# 008.net
KiCad netlist of a schematic drawn in EAGLE
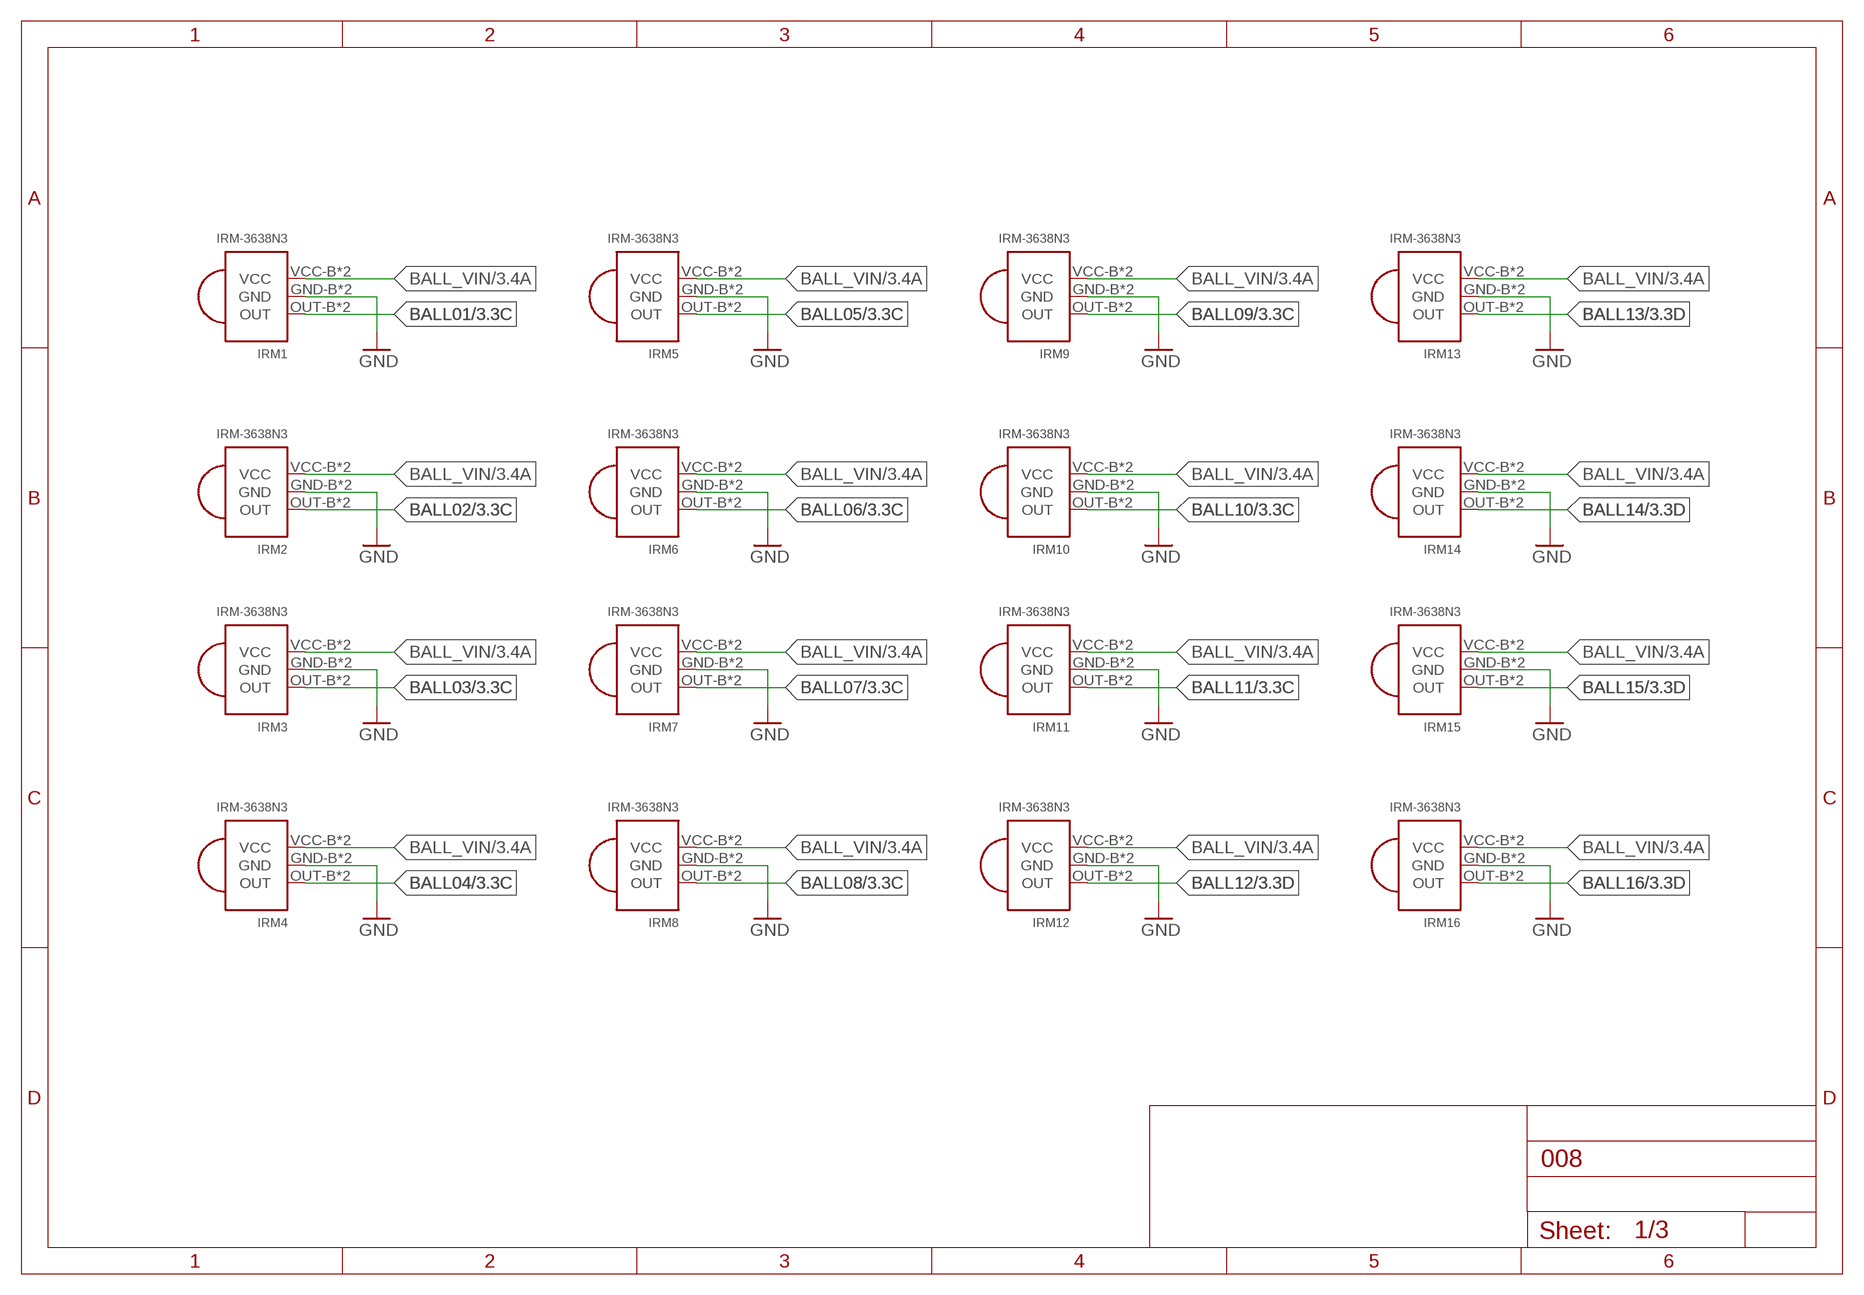
[diagram p0: schematic, sheet 1]
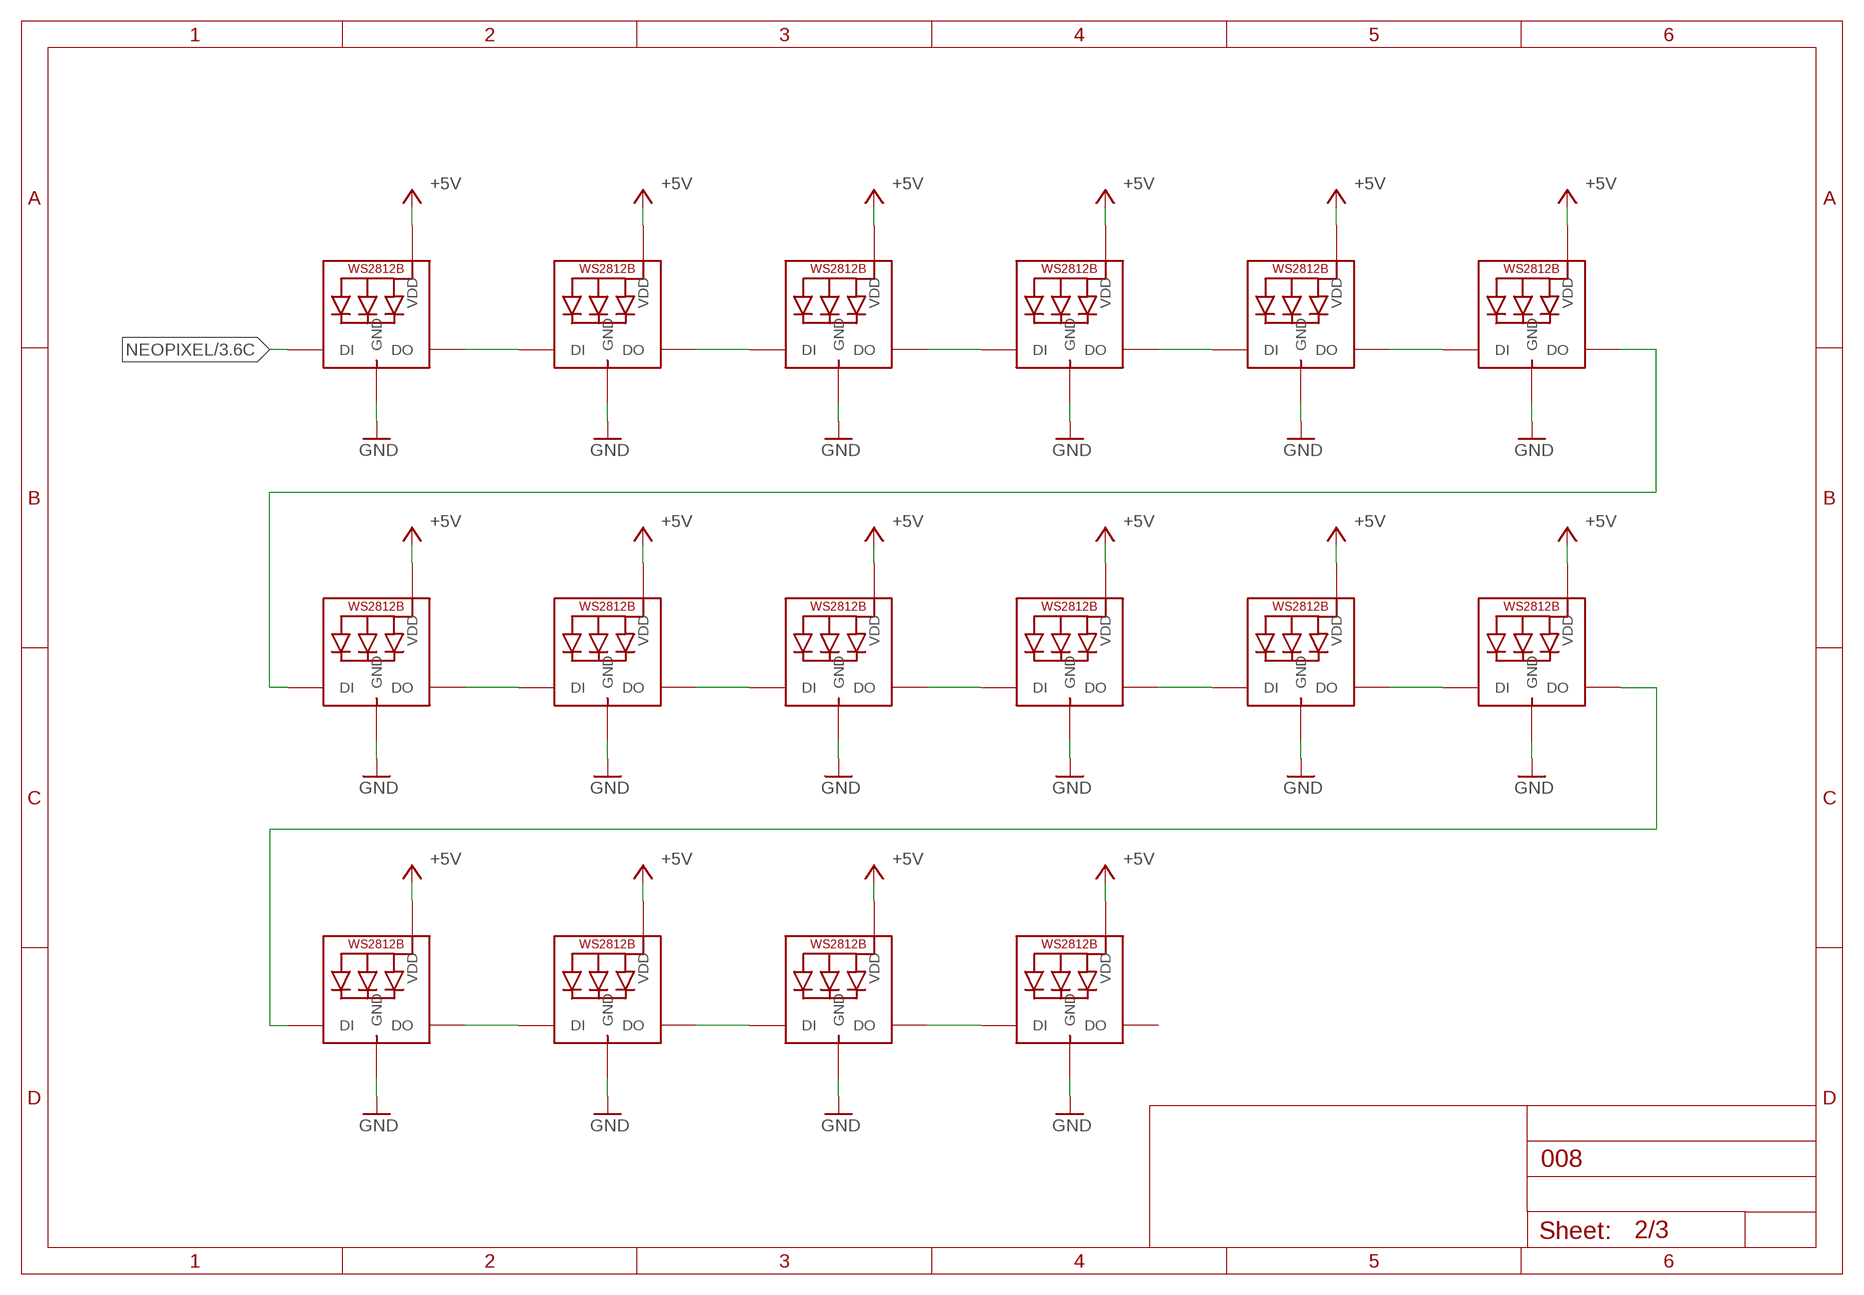
[diagram p1: schematic, sheet 2]
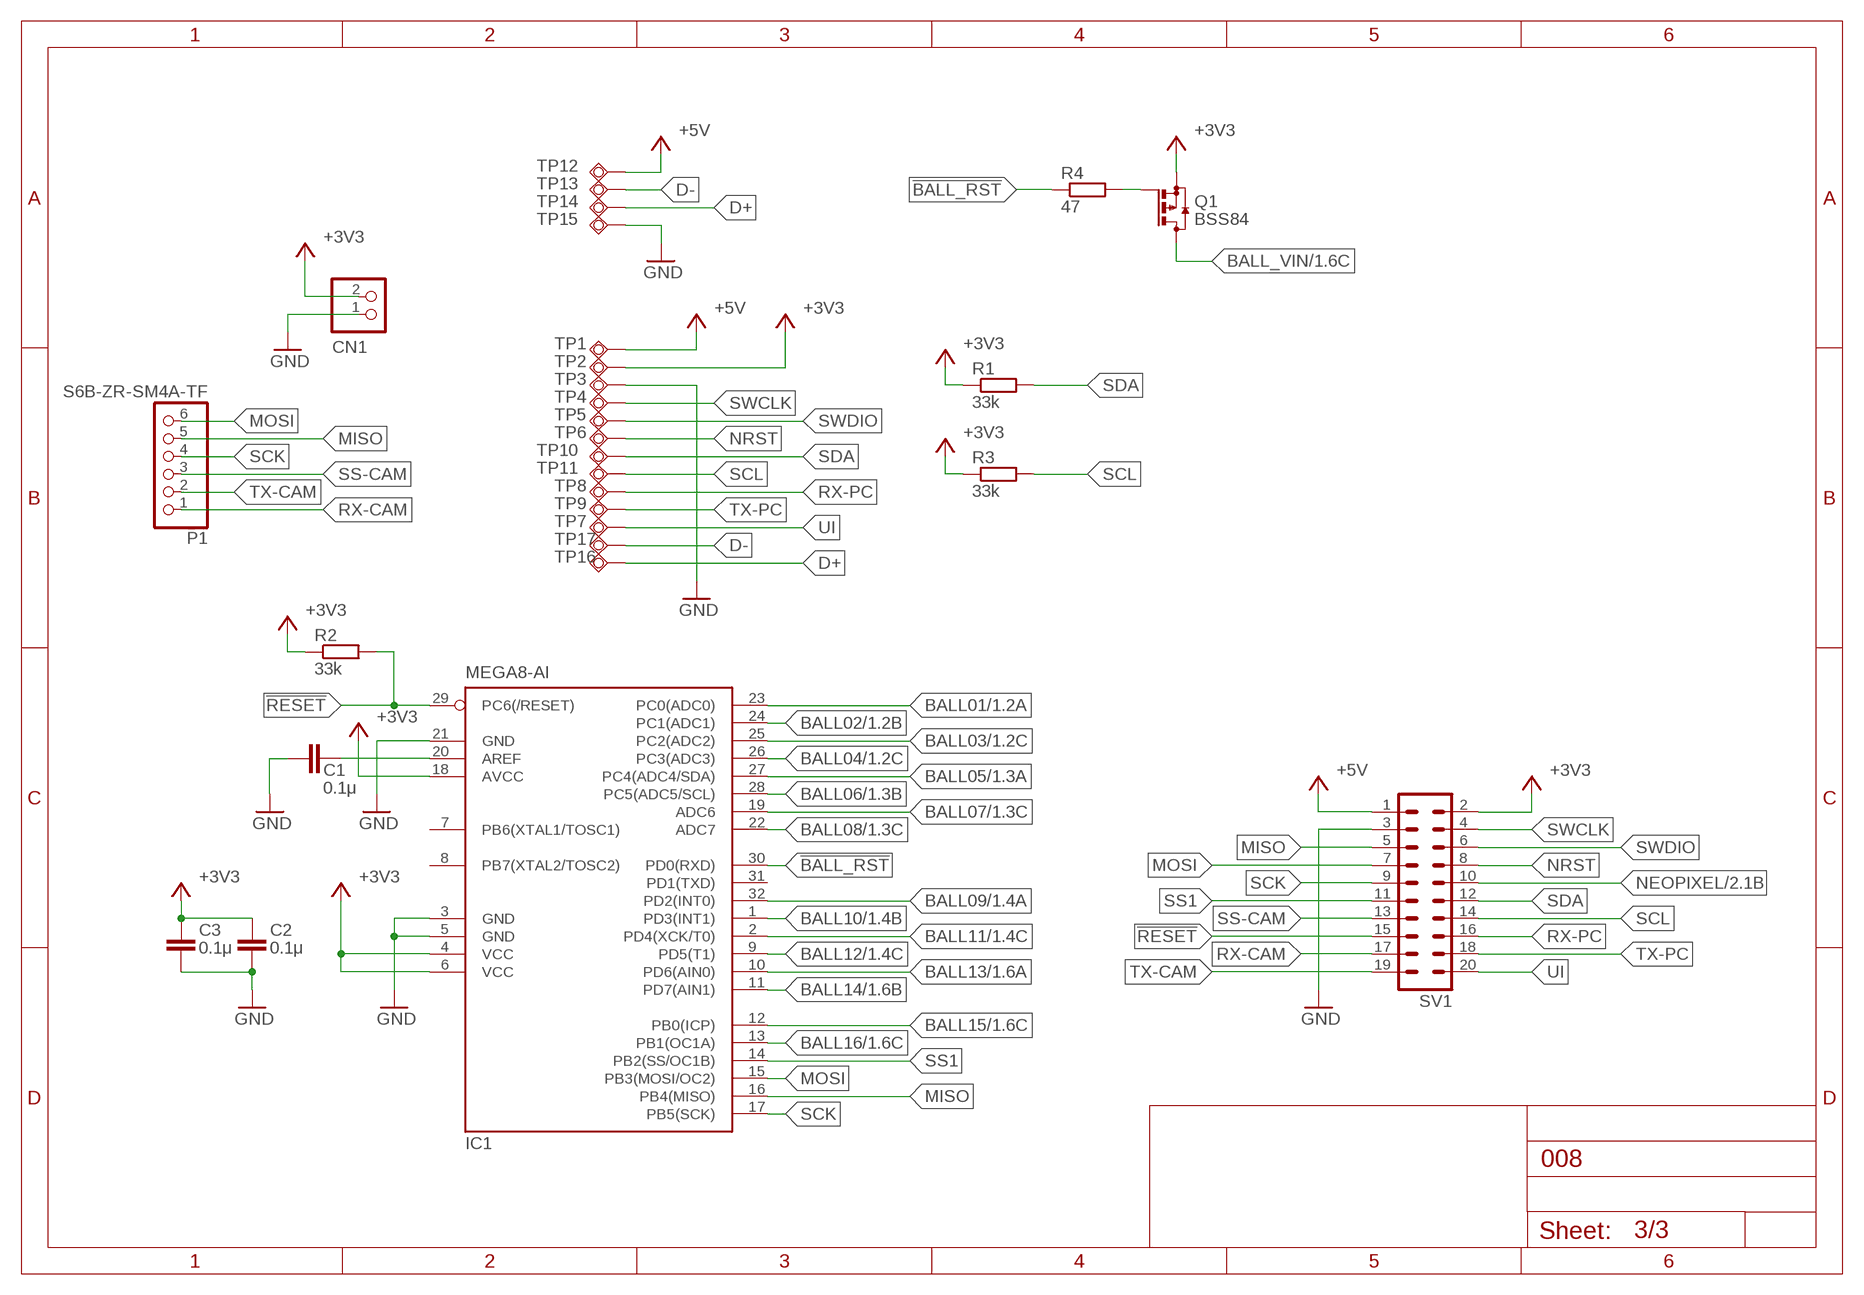
[diagram p2: schematic, sheet 3]

(export (version "E")
  (design (tool "Eeschema 10.0.6"))
  (components
    (comp (ref "LED1")
      (value "WS2812B5050")
      (footprint "eagle-import:WS2812B")
      (libsource (lib "eagle-import") (part "WS2812B5050"))
    )
    (comp (ref "LED2")
      (value "WS2812B5050")
      (footprint "eagle-import:WS2812B")
      (libsource (lib "eagle-import") (part "WS2812B5050"))
    )
    (comp (ref "LED3")
      (value "WS2812B5050")
      (footprint "eagle-import:WS2812B")
      (libsource (lib "eagle-import") (part "WS2812B5050"))
    )
    (comp (ref "LED4")
      (value "WS2812B5050")
      (footprint "eagle-import:WS2812B")
      (libsource (lib "eagle-import") (part "WS2812B5050"))
    )
    (comp (ref "LED5")
      (value "WS2812B5050")
      (footprint "eagle-import:WS2812B")
      (libsource (lib "eagle-import") (part "WS2812B5050"))
    )
    (comp (ref "LED6")
      (value "WS2812B5050")
      (footprint "eagle-import:WS2812B")
      (libsource (lib "eagle-import") (part "WS2812B5050"))
    )
    (comp (ref "LED7")
      (value "WS2812B5050")
      (footprint "eagle-import:WS2812B")
      (libsource (lib "eagle-import") (part "WS2812B5050"))
    )
    (comp (ref "LED8")
      (value "WS2812B5050")
      (footprint "eagle-import:WS2812B")
      (libsource (lib "eagle-import") (part "WS2812B5050"))
    )
    (comp (ref "LED9")
      (value "WS2812B5050")
      (footprint "eagle-import:WS2812B")
      (libsource (lib "eagle-import") (part "WS2812B5050"))
    )
    (comp (ref "LED10")
      (value "WS2812B5050")
      (footprint "eagle-import:WS2812B")
      (libsource (lib "eagle-import") (part "WS2812B5050"))
    )
    (comp (ref "LED11")
      (value "WS2812B5050")
      (footprint "eagle-import:WS2812B")
      (libsource (lib "eagle-import") (part "WS2812B5050"))
    )
    (comp (ref "LED12")
      (value "WS2812B5050")
      (footprint "eagle-import:WS2812B")
      (libsource (lib "eagle-import") (part "WS2812B5050"))
    )
    (comp (ref "LED13")
      (value "WS2812B5050")
      (footprint "eagle-import:WS2812B")
      (libsource (lib "eagle-import") (part "WS2812B5050"))
    )
    (comp (ref "LED14")
      (value "WS2812B5050")
      (footprint "eagle-import:WS2812B")
      (libsource (lib "eagle-import") (part "WS2812B5050"))
    )
    (comp (ref "LED15")
      (value "WS2812B5050")
      (footprint "eagle-import:WS2812B")
      (libsource (lib "eagle-import") (part "WS2812B5050"))
    )
    (comp (ref "LED16")
      (value "WS2812B5050")
      (footprint "eagle-import:WS2812B")
      (libsource (lib "eagle-import") (part "WS2812B5050"))
    )
    (comp (ref "C1")
      (value "0.1μ")
      (footprint "eagle-import:C1608")
      (libsource (lib "eagle-import") (part "C-EUC1608"))
    )
    (comp (ref "C2")
      (value "0.1μ")
      (footprint "eagle-import:C1608")
      (libsource (lib "eagle-import") (part "C-EUC1608"))
    )
    (comp (ref "C3")
      (value "0.1μ")
      (footprint "eagle-import:C1608")
      (libsource (lib "eagle-import") (part "C-EUC1608"))
    )
    (comp (ref "CN1")
      (value "S2B-PH-SM4-TB")
      (footprint "eagle-import:S2B-PH-SM4-TB")
      (libsource (lib "eagle-import") (part "S2B-PH-SM4-TB"))
    )
    (comp (ref "IC1")
      (value "MEGA8-AI")
      (footprint "eagle-import:TQFP32-08")
      (fields (field (name "MPN") "ATMEGA8-16AU"))
      (libsource (lib "eagle-import") (part "MEGA8-AI"))
    )
    (comp (ref "P1")
      (value "S6B-ZR-SM4A-TF")
      (footprint "eagle-import:ZH-SM4-SIDE06")
      (libsource (lib "eagle-import") (part "S6B-ZR-SM4A-TF"))
    )
    (comp (ref "Q1")
      (value "BSS84")
      (footprint "eagle-import:SOT23")
      (libsource (lib "eagle-import") (part "BSS84"))
    )
    (comp (ref "R1")
      (value "33k")
      (footprint "eagle-import:R0603")
      (libsource (lib "eagle-import") (part "R-EU_R0603"))
    )
    (comp (ref "R2")
      (value "33k")
      (footprint "eagle-import:R0603")
      (libsource (lib "eagle-import") (part "R-EU_R0603"))
    )
    (comp (ref "R3")
      (value "33k")
      (footprint "eagle-import:R0603")
      (libsource (lib "eagle-import") (part "R-EU_R0603"))
    )
    (comp (ref "R4")
      (value "47")
      (footprint "eagle-import:R0603")
      (libsource (lib "eagle-import") (part "R-EU_R0603"))
    )
    (comp (ref "SV1")
      (value "ML20")
      (footprint "eagle-import:ML20")
      (libsource (lib "eagle-import") (part "ML20"))
    )
    (comp (ref "TP1")
      (value "TPSQTP10SQ")
      (footprint "eagle-import:TP10SQ")
      (libsource (lib "eagle-import") (part "TPSQTP10SQ"))
    )
    (comp (ref "TP2")
      (value "TPSQTP10R")
      (footprint "eagle-import:TP10R")
      (libsource (lib "eagle-import") (part "TPSQTP10R"))
    )
    (comp (ref "TP3")
      (value "TPSQTP10R")
      (footprint "eagle-import:TP10R")
      (libsource (lib "eagle-import") (part "TPSQTP10R"))
    )
    (comp (ref "TP4")
      (value "TPSQTP10R")
      (footprint "eagle-import:TP10R")
      (libsource (lib "eagle-import") (part "TPSQTP10R"))
    )
    (comp (ref "TP5")
      (value "TPSQTP10R")
      (footprint "eagle-import:TP10R")
      (libsource (lib "eagle-import") (part "TPSQTP10R"))
    )
    (comp (ref "TP6")
      (value "TPSQTP10R")
      (footprint "eagle-import:TP10R")
      (libsource (lib "eagle-import") (part "TPSQTP10R"))
    )
    (comp (ref "TP7")
      (value "TPSQTP10R")
      (footprint "eagle-import:TP10R")
      (libsource (lib "eagle-import") (part "TPSQTP10R"))
    )
    (comp (ref "TP8")
      (value "TPSQTP10R")
      (footprint "eagle-import:TP10R")
      (libsource (lib "eagle-import") (part "TPSQTP10R"))
    )
    (comp (ref "TP9")
      (value "TPSQTP10R")
      (footprint "eagle-import:TP10R")
      (libsource (lib "eagle-import") (part "TPSQTP10R"))
    )
    (comp (ref "TP10")
      (value "TPSQTP10R")
      (footprint "eagle-import:TP10R")
      (libsource (lib "eagle-import") (part "TPSQTP10R"))
    )
    (comp (ref "TP11")
      (value "TPSQTP10R")
      (footprint "eagle-import:TP10R")
      (libsource (lib "eagle-import") (part "TPSQTP10R"))
    )
    (comp (ref "TP12")
      (value "TPSQTP10SQ")
      (footprint "eagle-import:TP10SQ")
      (libsource (lib "eagle-import") (part "TPSQTP10SQ"))
    )
    (comp (ref "TP13")
      (value "TPSQTP10R")
      (footprint "eagle-import:TP10R")
      (libsource (lib "eagle-import") (part "TPSQTP10R"))
    )
    (comp (ref "TP14")
      (value "TPSQTP10R")
      (footprint "eagle-import:TP10R")
      (libsource (lib "eagle-import") (part "TPSQTP10R"))
    )
    (comp (ref "TP15")
      (value "TPSQTP10R")
      (footprint "eagle-import:TP10R")
      (libsource (lib "eagle-import") (part "TPSQTP10R"))
    )
    (comp (ref "TP16")
      (value "TPSQTP10R")
      (footprint "eagle-import:TP10R")
      (libsource (lib "eagle-import") (part "TPSQTP10R"))
    )
    (comp (ref "TP17")
      (value "TPSQTP10R")
      (footprint "eagle-import:TP10R")
      (libsource (lib "eagle-import") (part "TPSQTP10R"))
    )
    (comp (ref "IRM1")
      (value "IRM-3638N3")
      (footprint "eagle-import:MYPARTS_IRM_3633N3")
      (libsource (lib "eagle-import") (part "MYPARTS_IRM_3633N3IRM"))
    )
    (comp (ref "IRM2")
      (value "IRM-3638N3")
      (footprint "eagle-import:MYPARTS_IRM_3633N3")
      (libsource (lib "eagle-import") (part "MYPARTS_IRM_3633N3IRM"))
    )
    (comp (ref "IRM3")
      (value "IRM-3638N3")
      (footprint "eagle-import:MYPARTS_IRM_3633N3")
      (libsource (lib "eagle-import") (part "MYPARTS_IRM_3633N3IRM"))
    )
    (comp (ref "IRM4")
      (value "IRM-3638N3")
      (footprint "eagle-import:MYPARTS_IRM_3633N3")
      (libsource (lib "eagle-import") (part "MYPARTS_IRM_3633N3IRM"))
    )
    (comp (ref "IRM5")
      (value "IRM-3638N3")
      (footprint "eagle-import:MYPARTS_IRM_3633N3")
      (libsource (lib "eagle-import") (part "MYPARTS_IRM_3633N3IRM"))
    )
    (comp (ref "IRM6")
      (value "IRM-3638N3")
      (footprint "eagle-import:MYPARTS_IRM_3633N3")
      (libsource (lib "eagle-import") (part "MYPARTS_IRM_3633N3IRM"))
    )
    (comp (ref "IRM7")
      (value "IRM-3638N3")
      (footprint "eagle-import:MYPARTS_IRM_3633N3")
      (libsource (lib "eagle-import") (part "MYPARTS_IRM_3633N3IRM"))
    )
    (comp (ref "IRM8")
      (value "IRM-3638N3")
      (footprint "eagle-import:MYPARTS_IRM_3633N3")
      (libsource (lib "eagle-import") (part "MYPARTS_IRM_3633N3IRM"))
    )
    (comp (ref "IRM9")
      (value "IRM-3638N3")
      (footprint "eagle-import:MYPARTS_IRM_3633N3")
      (libsource (lib "eagle-import") (part "MYPARTS_IRM_3633N3IRM"))
    )
    (comp (ref "IRM10")
      (value "IRM-3638N3")
      (footprint "eagle-import:MYPARTS_IRM_3633N3")
      (libsource (lib "eagle-import") (part "MYPARTS_IRM_3633N3IRM"))
    )
    (comp (ref "IRM11")
      (value "IRM-3638N3")
      (footprint "eagle-import:MYPARTS_IRM_3633N3")
      (libsource (lib "eagle-import") (part "MYPARTS_IRM_3633N3IRM"))
    )
    (comp (ref "IRM12")
      (value "IRM-3638N3")
      (footprint "eagle-import:MYPARTS_IRM_3633N3")
      (libsource (lib "eagle-import") (part "MYPARTS_IRM_3633N3IRM"))
    )
    (comp (ref "IRM13")
      (value "IRM-3638N3")
      (footprint "eagle-import:MYPARTS_IRM_3633N3")
      (libsource (lib "eagle-import") (part "MYPARTS_IRM_3633N3IRM"))
    )
    (comp (ref "IRM14")
      (value "IRM-3638N3")
      (footprint "eagle-import:MYPARTS_IRM_3633N3")
      (libsource (lib "eagle-import") (part "MYPARTS_IRM_3633N3IRM"))
    )
    (comp (ref "IRM15")
      (value "IRM-3638N3")
      (footprint "eagle-import:MYPARTS_IRM_3633N3")
      (libsource (lib "eagle-import") (part "MYPARTS_IRM_3633N3IRM"))
    )
    (comp (ref "IRM16")
      (value "IRM-3638N3")
      (footprint "eagle-import:MYPARTS_IRM_3633N3")
      (libsource (lib "eagle-import") (part "MYPARTS_IRM_3633N3IRM"))
    )
  )
  (nets
    (net (code "1") (name "+3V3") (class "Default")
      (node (ref "C2") (pin "1") (pinfunction "1_1") (pintype "passive"))
      (node (ref "C3") (pin "1") (pinfunction "1_1") (pintype "passive"))
      (node (ref "CN1") (pin "2") (pinfunction "2_2") (pintype "passive"))
      (node (ref "IC1") (pin "18") (pinfunction "AVCC_18") (pintype "power_in"))
      (node (ref "IC1") (pin "4") (pinfunction "VCC_4") (pintype "power_in"))
      (node (ref "IC1") (pin "6") (pinfunction "VCC_6") (pintype "power_in"))
      (node (ref "Q1") (pin "2") (pinfunction "S_2") (pintype "passive"))
      (node (ref "R1") (pin "1") (pinfunction "1_1") (pintype "passive"))
      (node (ref "R2") (pin "1") (pinfunction "1_1") (pintype "passive"))
      (node (ref "R3") (pin "1") (pinfunction "1_1") (pintype "passive"))
      (node (ref "SV1") (pin "2") (pinfunction "2_2") (pintype "passive"))
      (node (ref "TP2") (pin "TP") (pinfunction "TP_TP") (pintype "input"))
    )
    (net (code "2") (name "+5V") (class "Default")
      (node (ref "LED1") (pin "1-VDD") (pinfunction "VDD_1-VDD") (pintype "power_in"))
      (node (ref "LED10") (pin "1-VDD") (pinfunction "VDD_1-VDD") (pintype "power_in"))
      (node (ref "LED11") (pin "1-VDD") (pinfunction "VDD_1-VDD") (pintype "power_in"))
      (node (ref "LED12") (pin "1-VDD") (pinfunction "VDD_1-VDD") (pintype "power_in"))
      (node (ref "LED13") (pin "1-VDD") (pinfunction "VDD_1-VDD") (pintype "power_in"))
      (node (ref "LED14") (pin "1-VDD") (pinfunction "VDD_1-VDD") (pintype "power_in"))
      (node (ref "LED15") (pin "1-VDD") (pinfunction "VDD_1-VDD") (pintype "power_in"))
      (node (ref "LED16") (pin "1-VDD") (pinfunction "VDD_1-VDD") (pintype "power_in"))
      (node (ref "LED2") (pin "1-VDD") (pinfunction "VDD_1-VDD") (pintype "power_in"))
      (node (ref "LED3") (pin "1-VDD") (pinfunction "VDD_1-VDD") (pintype "power_in"))
      (node (ref "LED4") (pin "1-VDD") (pinfunction "VDD_1-VDD") (pintype "power_in"))
      (node (ref "LED5") (pin "1-VDD") (pinfunction "VDD_1-VDD") (pintype "power_in"))
      (node (ref "LED6") (pin "1-VDD") (pinfunction "VDD_1-VDD") (pintype "power_in"))
      (node (ref "LED7") (pin "1-VDD") (pinfunction "VDD_1-VDD") (pintype "power_in"))
      (node (ref "LED8") (pin "1-VDD") (pinfunction "VDD_1-VDD") (pintype "power_in"))
      (node (ref "LED9") (pin "1-VDD") (pinfunction "VDD_1-VDD") (pintype "power_in"))
      (node (ref "SV1") (pin "1") (pinfunction "1_1") (pintype "passive"))
      (node (ref "TP1") (pin "TP") (pinfunction "TP_TP") (pintype "input"))
      (node (ref "TP12") (pin "TP") (pinfunction "TP_TP") (pintype "input"))
    )
    (net (code "3") (name "BALL01") (class "Default")
      (node (ref "IC1") (pin "23") (pinfunction "PC0(ADC0)_23") (pintype "bidirectional"))
      (node (ref "IRM1") (pin "OUT-B") (pinfunction "OUT_OUT-B") (pintype "bidirectional"))
      (node (ref "IRM1") (pin "OUT-T") (pinfunction "OUT_OUT-T") (pintype "bidirectional"))
    )
    (net (code "4") (name "BALL02") (class "Default")
      (node (ref "IC1") (pin "24") (pinfunction "PC1(ADC1)_24") (pintype "bidirectional"))
      (node (ref "IRM2") (pin "OUT-B") (pinfunction "OUT_OUT-B") (pintype "bidirectional"))
      (node (ref "IRM2") (pin "OUT-T") (pinfunction "OUT_OUT-T") (pintype "bidirectional"))
    )
    (net (code "5") (name "BALL03") (class "Default")
      (node (ref "IC1") (pin "25") (pinfunction "PC2(ADC2)_25") (pintype "bidirectional"))
      (node (ref "IRM3") (pin "OUT-B") (pinfunction "OUT_OUT-B") (pintype "bidirectional"))
      (node (ref "IRM3") (pin "OUT-T") (pinfunction "OUT_OUT-T") (pintype "bidirectional"))
    )
    (net (code "6") (name "BALL04") (class "Default")
      (node (ref "IC1") (pin "26") (pinfunction "PC3(ADC3)_26") (pintype "bidirectional"))
      (node (ref "IRM4") (pin "OUT-B") (pinfunction "OUT_OUT-B") (pintype "bidirectional"))
      (node (ref "IRM4") (pin "OUT-T") (pinfunction "OUT_OUT-T") (pintype "bidirectional"))
    )
    (net (code "7") (name "BALL05") (class "Default")
      (node (ref "IC1") (pin "27") (pinfunction "PC4(ADC4/SDA)_27") (pintype "bidirectional"))
      (node (ref "IRM5") (pin "OUT-B") (pinfunction "OUT_OUT-B") (pintype "bidirectional"))
      (node (ref "IRM5") (pin "OUT-T") (pinfunction "OUT_OUT-T") (pintype "bidirectional"))
    )
    (net (code "8") (name "BALL06") (class "Default")
      (node (ref "IC1") (pin "28") (pinfunction "PC5(ADC5/SCL)_28") (pintype "bidirectional"))
      (node (ref "IRM6") (pin "OUT-B") (pinfunction "OUT_OUT-B") (pintype "bidirectional"))
      (node (ref "IRM6") (pin "OUT-T") (pinfunction "OUT_OUT-T") (pintype "bidirectional"))
    )
    (net (code "9") (name "BALL07") (class "Default")
      (node (ref "IC1") (pin "19") (pinfunction "ADC6_19") (pintype "bidirectional"))
      (node (ref "IRM7") (pin "OUT-B") (pinfunction "OUT_OUT-B") (pintype "bidirectional"))
      (node (ref "IRM7") (pin "OUT-T") (pinfunction "OUT_OUT-T") (pintype "bidirectional"))
    )
    (net (code "10") (name "BALL08") (class "Default")
      (node (ref "IC1") (pin "22") (pinfunction "ADC7_22") (pintype "bidirectional"))
      (node (ref "IRM8") (pin "OUT-B") (pinfunction "OUT_OUT-B") (pintype "bidirectional"))
      (node (ref "IRM8") (pin "OUT-T") (pinfunction "OUT_OUT-T") (pintype "bidirectional"))
    )
    (net (code "11") (name "BALL09") (class "Default")
      (node (ref "IC1") (pin "32") (pinfunction "PD2(INT0)_32") (pintype "bidirectional"))
      (node (ref "IRM9") (pin "OUT-B") (pinfunction "OUT_OUT-B") (pintype "bidirectional"))
      (node (ref "IRM9") (pin "OUT-T") (pinfunction "OUT_OUT-T") (pintype "bidirectional"))
    )
    (net (code "12") (name "BALL10") (class "Default")
      (node (ref "IC1") (pin "1") (pinfunction "PD3(INT1)_1") (pintype "bidirectional"))
      (node (ref "IRM10") (pin "OUT-B") (pinfunction "OUT_OUT-B") (pintype "bidirectional"))
      (node (ref "IRM10") (pin "OUT-T") (pinfunction "OUT_OUT-T") (pintype "bidirectional"))
    )
    (net (code "13") (name "BALL11") (class "Default")
      (node (ref "IC1") (pin "2") (pinfunction "PD4(XCK/T0)_2") (pintype "bidirectional"))
      (node (ref "IRM11") (pin "OUT-B") (pinfunction "OUT_OUT-B") (pintype "bidirectional"))
      (node (ref "IRM11") (pin "OUT-T") (pinfunction "OUT_OUT-T") (pintype "bidirectional"))
    )
    (net (code "14") (name "BALL12") (class "Default")
      (node (ref "IC1") (pin "9") (pinfunction "PD5(T1)_9") (pintype "bidirectional"))
      (node (ref "IRM12") (pin "OUT-B") (pinfunction "OUT_OUT-B") (pintype "bidirectional"))
      (node (ref "IRM12") (pin "OUT-T") (pinfunction "OUT_OUT-T") (pintype "bidirectional"))
    )
    (net (code "15") (name "BALL13") (class "Default")
      (node (ref "IC1") (pin "10") (pinfunction "PD6(AIN0)_10") (pintype "bidirectional"))
      (node (ref "IRM13") (pin "OUT-B") (pinfunction "OUT_OUT-B") (pintype "bidirectional"))
      (node (ref "IRM13") (pin "OUT-T") (pinfunction "OUT_OUT-T") (pintype "bidirectional"))
    )
    (net (code "16") (name "BALL14") (class "Default")
      (node (ref "IC1") (pin "11") (pinfunction "PD7(AIN1)_11") (pintype "bidirectional"))
      (node (ref "IRM14") (pin "OUT-B") (pinfunction "OUT_OUT-B") (pintype "bidirectional"))
      (node (ref "IRM14") (pin "OUT-T") (pinfunction "OUT_OUT-T") (pintype "bidirectional"))
    )
    (net (code "17") (name "BALL15") (class "Default")
      (node (ref "IC1") (pin "12") (pinfunction "PB0(ICP)_12") (pintype "bidirectional"))
      (node (ref "IRM15") (pin "OUT-B") (pinfunction "OUT_OUT-B") (pintype "bidirectional"))
      (node (ref "IRM15") (pin "OUT-T") (pinfunction "OUT_OUT-T") (pintype "bidirectional"))
    )
    (net (code "18") (name "BALL16") (class "Default")
      (node (ref "IC1") (pin "13") (pinfunction "PB1(OC1A)_13") (pintype "bidirectional"))
      (node (ref "IRM16") (pin "OUT-B") (pinfunction "OUT_OUT-B") (pintype "bidirectional"))
      (node (ref "IRM16") (pin "OUT-T") (pinfunction "OUT_OUT-T") (pintype "bidirectional"))
    )
    (net (code "19") (name "BALL_VIN") (class "Default")
      (node (ref "IRM1") (pin "VCC-B") (pinfunction "VCC_VCC-B") (pintype "bidirectional"))
      (node (ref "IRM1") (pin "VCC-T") (pinfunction "VCC_VCC-T") (pintype "bidirectional"))
      (node (ref "IRM10") (pin "VCC-B") (pinfunction "VCC_VCC-B") (pintype "bidirectional"))
      (node (ref "IRM10") (pin "VCC-T") (pinfunction "VCC_VCC-T") (pintype "bidirectional"))
      (node (ref "IRM11") (pin "VCC-B") (pinfunction "VCC_VCC-B") (pintype "bidirectional"))
      (node (ref "IRM11") (pin "VCC-T") (pinfunction "VCC_VCC-T") (pintype "bidirectional"))
      (node (ref "IRM12") (pin "VCC-B") (pinfunction "VCC_VCC-B") (pintype "bidirectional"))
      (node (ref "IRM12") (pin "VCC-T") (pinfunction "VCC_VCC-T") (pintype "bidirectional"))
      (node (ref "IRM13") (pin "VCC-B") (pinfunction "VCC_VCC-B") (pintype "bidirectional"))
      (node (ref "IRM13") (pin "VCC-T") (pinfunction "VCC_VCC-T") (pintype "bidirectional"))
      (node (ref "IRM14") (pin "VCC-B") (pinfunction "VCC_VCC-B") (pintype "bidirectional"))
      (node (ref "IRM14") (pin "VCC-T") (pinfunction "VCC_VCC-T") (pintype "bidirectional"))
      (node (ref "IRM15") (pin "VCC-B") (pinfunction "VCC_VCC-B") (pintype "bidirectional"))
      (node (ref "IRM15") (pin "VCC-T") (pinfunction "VCC_VCC-T") (pintype "bidirectional"))
      (node (ref "IRM16") (pin "VCC-B") (pinfunction "VCC_VCC-B") (pintype "bidirectional"))
      (node (ref "IRM16") (pin "VCC-T") (pinfunction "VCC_VCC-T") (pintype "bidirectional"))
      (node (ref "IRM2") (pin "VCC-B") (pinfunction "VCC_VCC-B") (pintype "bidirectional"))
      (node (ref "IRM2") (pin "VCC-T") (pinfunction "VCC_VCC-T") (pintype "bidirectional"))
      (node (ref "IRM3") (pin "VCC-B") (pinfunction "VCC_VCC-B") (pintype "bidirectional"))
      (node (ref "IRM3") (pin "VCC-T") (pinfunction "VCC_VCC-T") (pintype "bidirectional"))
      (node (ref "IRM4") (pin "VCC-B") (pinfunction "VCC_VCC-B") (pintype "bidirectional"))
      (node (ref "IRM4") (pin "VCC-T") (pinfunction "VCC_VCC-T") (pintype "bidirectional"))
      (node (ref "IRM5") (pin "VCC-B") (pinfunction "VCC_VCC-B") (pintype "bidirectional"))
      (node (ref "IRM5") (pin "VCC-T") (pinfunction "VCC_VCC-T") (pintype "bidirectional"))
      (node (ref "IRM6") (pin "VCC-B") (pinfunction "VCC_VCC-B") (pintype "bidirectional"))
      (node (ref "IRM6") (pin "VCC-T") (pinfunction "VCC_VCC-T") (pintype "bidirectional"))
      (node (ref "IRM7") (pin "VCC-B") (pinfunction "VCC_VCC-B") (pintype "bidirectional"))
      (node (ref "IRM7") (pin "VCC-T") (pinfunction "VCC_VCC-T") (pintype "bidirectional"))
      (node (ref "IRM8") (pin "VCC-B") (pinfunction "VCC_VCC-B") (pintype "bidirectional"))
      (node (ref "IRM8") (pin "VCC-T") (pinfunction "VCC_VCC-T") (pintype "bidirectional"))
      (node (ref "IRM9") (pin "VCC-B") (pinfunction "VCC_VCC-B") (pintype "bidirectional"))
      (node (ref "IRM9") (pin "VCC-T") (pinfunction "VCC_VCC-T") (pintype "bidirectional"))
      (node (ref "Q1") (pin "3") (pinfunction "D_3") (pintype "passive"))
    )
    (net (code "20") (name "D+") (class "Default")
      (node (ref "TP14") (pin "TP") (pinfunction "TP_TP") (pintype "input"))
      (node (ref "TP16") (pin "TP") (pinfunction "TP_TP") (pintype "input"))
    )
    (net (code "21") (name "D-") (class "Default")
      (node (ref "TP13") (pin "TP") (pinfunction "TP_TP") (pintype "input"))
      (node (ref "TP17") (pin "TP") (pinfunction "TP_TP") (pintype "input"))
    )
    (net (code "22") (name "GND") (class "Default")
      (node (ref "C1") (pin "2") (pinfunction "2_2") (pintype "passive"))
      (node (ref "C2") (pin "2") (pinfunction "2_2") (pintype "passive"))
      (node (ref "C3") (pin "2") (pinfunction "2_2") (pintype "passive"))
      (node (ref "CN1") (pin "1") (pinfunction "1_1") (pintype "passive"))
      (node (ref "IC1") (pin "21") (pinfunction "GND_21") (pintype "power_in"))
      (node (ref "IC1") (pin "3") (pinfunction "GND_3") (pintype "power_in"))
      (node (ref "IC1") (pin "5") (pinfunction "GND_5") (pintype "power_in"))
      (node (ref "IRM1") (pin "GND-B") (pinfunction "GND_GND-B") (pintype "bidirectional"))
      (node (ref "IRM1") (pin "GND-T") (pinfunction "GND_GND-T") (pintype "bidirectional"))
      (node (ref "IRM10") (pin "GND-B") (pinfunction "GND_GND-B") (pintype "bidirectional"))
      (node (ref "IRM10") (pin "GND-T") (pinfunction "GND_GND-T") (pintype "bidirectional"))
      (node (ref "IRM11") (pin "GND-B") (pinfunction "GND_GND-B") (pintype "bidirectional"))
      (node (ref "IRM11") (pin "GND-T") (pinfunction "GND_GND-T") (pintype "bidirectional"))
      (node (ref "IRM12") (pin "GND-B") (pinfunction "GND_GND-B") (pintype "bidirectional"))
      (node (ref "IRM12") (pin "GND-T") (pinfunction "GND_GND-T") (pintype "bidirectional"))
      (node (ref "IRM13") (pin "GND-B") (pinfunction "GND_GND-B") (pintype "bidirectional"))
      (node (ref "IRM13") (pin "GND-T") (pinfunction "GND_GND-T") (pintype "bidirectional"))
      (node (ref "IRM14") (pin "GND-B") (pinfunction "GND_GND-B") (pintype "bidirectional"))
      (node (ref "IRM14") (pin "GND-T") (pinfunction "GND_GND-T") (pintype "bidirectional"))
      (node (ref "IRM15") (pin "GND-B") (pinfunction "GND_GND-B") (pintype "bidirectional"))
      (node (ref "IRM15") (pin "GND-T") (pinfunction "GND_GND-T") (pintype "bidirectional"))
      (node (ref "IRM16") (pin "GND-B") (pinfunction "GND_GND-B") (pintype "bidirectional"))
      (node (ref "IRM16") (pin "GND-T") (pinfunction "GND_GND-T") (pintype "bidirectional"))
      (node (ref "IRM2") (pin "GND-B") (pinfunction "GND_GND-B") (pintype "bidirectional"))
      (node (ref "IRM2") (pin "GND-T") (pinfunction "GND_GND-T") (pintype "bidirectional"))
      (node (ref "IRM3") (pin "GND-B") (pinfunction "GND_GND-B") (pintype "bidirectional"))
      (node (ref "IRM3") (pin "GND-T") (pinfunction "GND_GND-T") (pintype "bidirectional"))
      (node (ref "IRM4") (pin "GND-B") (pinfunction "GND_GND-B") (pintype "bidirectional"))
      (node (ref "IRM4") (pin "GND-T") (pinfunction "GND_GND-T") (pintype "bidirectional"))
      (node (ref "IRM5") (pin "GND-B") (pinfunction "GND_GND-B") (pintype "bidirectional"))
      (node (ref "IRM5") (pin "GND-T") (pinfunction "GND_GND-T") (pintype "bidirectional"))
      (node (ref "IRM6") (pin "GND-B") (pinfunction "GND_GND-B") (pintype "bidirectional"))
      (node (ref "IRM6") (pin "GND-T") (pinfunction "GND_GND-T") (pintype "bidirectional"))
      (node (ref "IRM7") (pin "GND-B") (pinfunction "GND_GND-B") (pintype "bidirectional"))
      (node (ref "IRM7") (pin "GND-T") (pinfunction "GND_GND-T") (pintype "bidirectional"))
      (node (ref "IRM8") (pin "GND-B") (pinfunction "GND_GND-B") (pintype "bidirectional"))
      (node (ref "IRM8") (pin "GND-T") (pinfunction "GND_GND-T") (pintype "bidirectional"))
      (node (ref "IRM9") (pin "GND-B") (pinfunction "GND_GND-B") (pintype "bidirectional"))
      (node (ref "IRM9") (pin "GND-T") (pinfunction "GND_GND-T") (pintype "bidirectional"))
      (node (ref "LED1") (pin "3-GND") (pinfunction "GND_3-GND") (pintype "power_in"))
      (node (ref "LED10") (pin "3-GND") (pinfunction "GND_3-GND") (pintype "power_in"))
      (node (ref "LED11") (pin "3-GND") (pinfunction "GND_3-GND") (pintype "power_in"))
      (node (ref "LED12") (pin "3-GND") (pinfunction "GND_3-GND") (pintype "power_in"))
      (node (ref "LED13") (pin "3-GND") (pinfunction "GND_3-GND") (pintype "power_in"))
      (node (ref "LED14") (pin "3-GND") (pinfunction "GND_3-GND") (pintype "power_in"))
      (node (ref "LED15") (pin "3-GND") (pinfunction "GND_3-GND") (pintype "power_in"))
      (node (ref "LED16") (pin "3-GND") (pinfunction "GND_3-GND") (pintype "power_in"))
      (node (ref "LED2") (pin "3-GND") (pinfunction "GND_3-GND") (pintype "power_in"))
      (node (ref "LED3") (pin "3-GND") (pinfunction "GND_3-GND") (pintype "power_in"))
      (node (ref "LED4") (pin "3-GND") (pinfunction "GND_3-GND") (pintype "power_in"))
      (node (ref "LED5") (pin "3-GND") (pinfunction "GND_3-GND") (pintype "power_in"))
      (node (ref "LED6") (pin "3-GND") (pinfunction "GND_3-GND") (pintype "power_in"))
      (node (ref "LED7") (pin "3-GND") (pinfunction "GND_3-GND") (pintype "power_in"))
      (node (ref "LED8") (pin "3-GND") (pinfunction "GND_3-GND") (pintype "power_in"))
      (node (ref "LED9") (pin "3-GND") (pinfunction "GND_3-GND") (pintype "power_in"))
      (node (ref "SV1") (pin "3") (pinfunction "3_3") (pintype "passive"))
      (node (ref "TP15") (pin "TP") (pinfunction "TP_TP") (pintype "input"))
      (node (ref "TP3") (pin "TP") (pinfunction "TP_TP") (pintype "input"))
    )
    (net (code "23") (name "MISO") (class "Default")
      (node (ref "IC1") (pin "16") (pinfunction "PB4(MISO)_16") (pintype "bidirectional"))
      (node (ref "P1") (pin "5") (pinfunction "5_5") (pintype "passive"))
      (node (ref "SV1") (pin "5") (pinfunction "5_5") (pintype "passive"))
    )
    (net (code "24") (name "MOSI") (class "Default")
      (node (ref "IC1") (pin "15") (pinfunction "PB3(MOSI/OC2)_15") (pintype "bidirectional"))
      (node (ref "P1") (pin "6") (pinfunction "6_6") (pintype "passive"))
      (node (ref "SV1") (pin "7") (pinfunction "7_7") (pintype "passive"))
    )
    (net (code "25") (name "NEOPIXEL") (class "Default")
      (node (ref "LED1") (pin "4-DIN") (pinfunction "DI_4-DIN") (pintype "input"))
      (node (ref "SV1") (pin "10") (pinfunction "10_10") (pintype "passive"))
    )
    (net (code "26") (name "NRST") (class "Default")
      (node (ref "SV1") (pin "8") (pinfunction "8_8") (pintype "passive"))
      (node (ref "TP6") (pin "TP") (pinfunction "TP_TP") (pintype "input"))
    )
    (net (code "27") (name "Net-(IC1-AREF)") (class "Default")
      (node (ref "C1") (pin "1") (pinfunction "1_1") (pintype "passive"))
      (node (ref "IC1") (pin "20") (pinfunction "AREF_20") (pintype "passive"))
    )
    (net (code "28") (name "Net-(LED1-DO)") (class "Default")
      (node (ref "LED1") (pin "2-DOUT") (pinfunction "DO_2-DOUT") (pintype "output"))
      (node (ref "LED2") (pin "4-DIN") (pinfunction "DI_4-DIN") (pintype "input"))
    )
    (net (code "29") (name "Net-(LED2-DO)") (class "Default")
      (node (ref "LED2") (pin "2-DOUT") (pinfunction "DO_2-DOUT") (pintype "output"))
      (node (ref "LED3") (pin "4-DIN") (pinfunction "DI_4-DIN") (pintype "input"))
    )
    (net (code "30") (name "Net-(LED3-DO)") (class "Default")
      (node (ref "LED3") (pin "2-DOUT") (pinfunction "DO_2-DOUT") (pintype "output"))
      (node (ref "LED4") (pin "4-DIN") (pinfunction "DI_4-DIN") (pintype "input"))
    )
    (net (code "31") (name "Net-(LED4-DO)") (class "Default")
      (node (ref "LED4") (pin "2-DOUT") (pinfunction "DO_2-DOUT") (pintype "output"))
      (node (ref "LED5") (pin "4-DIN") (pinfunction "DI_4-DIN") (pintype "input"))
    )
    (net (code "32") (name "Net-(LED5-DO)") (class "Default")
      (node (ref "LED5") (pin "2-DOUT") (pinfunction "DO_2-DOUT") (pintype "output"))
      (node (ref "LED6") (pin "4-DIN") (pinfunction "DI_4-DIN") (pintype "input"))
    )
    (net (code "33") (name "Net-(LED6-DO)") (class "Default")
      (node (ref "LED6") (pin "2-DOUT") (pinfunction "DO_2-DOUT") (pintype "output"))
      (node (ref "LED7") (pin "4-DIN") (pinfunction "DI_4-DIN") (pintype "input"))
    )
    (net (code "34") (name "Net-(LED7-DO)") (class "Default")
      (node (ref "LED7") (pin "2-DOUT") (pinfunction "DO_2-DOUT") (pintype "output"))
      (node (ref "LED8") (pin "4-DIN") (pinfunction "DI_4-DIN") (pintype "input"))
    )
    (net (code "35") (name "Net-(LED8-DO)") (class "Default")
      (node (ref "LED8") (pin "2-DOUT") (pinfunction "DO_2-DOUT") (pintype "output"))
      (node (ref "LED9") (pin "4-DIN") (pinfunction "DI_4-DIN") (pintype "input"))
    )
    (net (code "36") (name "Net-(LED10-DI)") (class "Default")
      (node (ref "LED10") (pin "4-DIN") (pinfunction "DI_4-DIN") (pintype "input"))
      (node (ref "LED9") (pin "2-DOUT") (pinfunction "DO_2-DOUT") (pintype "output"))
    )
    (net (code "37") (name "Net-(LED10-DO)") (class "Default")
      (node (ref "LED10") (pin "2-DOUT") (pinfunction "DO_2-DOUT") (pintype "output"))
      (node (ref "LED11") (pin "4-DIN") (pinfunction "DI_4-DIN") (pintype "input"))
    )
    (net (code "38") (name "Net-(LED11-DO)") (class "Default")
      (node (ref "LED11") (pin "2-DOUT") (pinfunction "DO_2-DOUT") (pintype "output"))
      (node (ref "LED12") (pin "4-DIN") (pinfunction "DI_4-DIN") (pintype "input"))
    )
    (net (code "39") (name "Net-(LED12-DO)") (class "Default")
      (node (ref "LED12") (pin "2-DOUT") (pinfunction "DO_2-DOUT") (pintype "output"))
      (node (ref "LED13") (pin "4-DIN") (pinfunction "DI_4-DIN") (pintype "input"))
    )
    (net (code "40") (name "Net-(LED13-DO)") (class "Default")
      (node (ref "LED13") (pin "2-DOUT") (pinfunction "DO_2-DOUT") (pintype "output"))
      (node (ref "LED14") (pin "4-DIN") (pinfunction "DI_4-DIN") (pintype "input"))
    )
    (net (code "41") (name "Net-(LED14-DO)") (class "Default")
      (node (ref "LED14") (pin "2-DOUT") (pinfunction "DO_2-DOUT") (pintype "output"))
      (node (ref "LED15") (pin "4-DIN") (pinfunction "DI_4-DIN") (pintype "input"))
    )
    (net (code "42") (name "Net-(LED15-DO)") (class "Default")
      (node (ref "LED15") (pin "2-DOUT") (pinfunction "DO_2-DOUT") (pintype "output"))
      (node (ref "LED16") (pin "4-DIN") (pinfunction "DI_4-DIN") (pintype "input"))
    )
    (net (code "43") (name "Net-(Q1-G)") (class "Default")
      (node (ref "Q1") (pin "1") (pinfunction "G_1") (pintype "passive"))
      (node (ref "R4") (pin "2") (pinfunction "2_2") (pintype "passive"))
    )
    (net (code "44") (name "RX-CAM") (class "Default")
      (node (ref "P1") (pin "1") (pinfunction "1_1") (pintype "passive"))
      (node (ref "SV1") (pin "17") (pinfunction "17_17") (pintype "passive"))
    )
    (net (code "45") (name "RX-PC") (class "Default")
      (node (ref "SV1") (pin "16") (pinfunction "16_16") (pintype "passive"))
      (node (ref "TP8") (pin "TP") (pinfunction "TP_TP") (pintype "input"))
    )
    (net (code "46") (name "SCK") (class "Default")
      (node (ref "IC1") (pin "17") (pinfunction "PB5(SCK)_17") (pintype "bidirectional"))
      (node (ref "P1") (pin "4") (pinfunction "4_4") (pintype "passive"))
      (node (ref "SV1") (pin "9") (pinfunction "9_9") (pintype "passive"))
    )
    (net (code "47") (name "SCL") (class "Default")
      (node (ref "R3") (pin "2") (pinfunction "2_2") (pintype "passive"))
      (node (ref "SV1") (pin "14") (pinfunction "14_14") (pintype "passive"))
      (node (ref "TP11") (pin "TP") (pinfunction "TP_TP") (pintype "input"))
    )
    (net (code "48") (name "SDA") (class "Default")
      (node (ref "R1") (pin "2") (pinfunction "2_2") (pintype "passive"))
      (node (ref "SV1") (pin "12") (pinfunction "12_12") (pintype "passive"))
      (node (ref "TP10") (pin "TP") (pinfunction "TP_TP") (pintype "input"))
    )
    (net (code "49") (name "SS-CAM") (class "Default")
      (node (ref "P1") (pin "3") (pinfunction "3_3") (pintype "passive"))
      (node (ref "SV1") (pin "13") (pinfunction "13_13") (pintype "passive"))
    )
    (net (code "50") (name "SS1") (class "Default")
      (node (ref "IC1") (pin "14") (pinfunction "PB2(SS/OC1B)_14") (pintype "bidirectional"))
      (node (ref "SV1") (pin "11") (pinfunction "11_11") (pintype "passive"))
    )
    (net (code "51") (name "SWCLK") (class "Default")
      (node (ref "SV1") (pin "4") (pinfunction "4_4") (pintype "passive"))
      (node (ref "TP4") (pin "TP") (pinfunction "TP_TP") (pintype "input"))
    )
    (net (code "52") (name "SWDIO") (class "Default")
      (node (ref "SV1") (pin "6") (pinfunction "6_6") (pintype "passive"))
      (node (ref "TP5") (pin "TP") (pinfunction "TP_TP") (pintype "input"))
    )
    (net (code "53") (name "TX-CAM") (class "Default")
      (node (ref "P1") (pin "2") (pinfunction "2_2") (pintype "passive"))
      (node (ref "SV1") (pin "19") (pinfunction "19_19") (pintype "passive"))
    )
    (net (code "54") (name "TX-PC") (class "Default")
      (node (ref "SV1") (pin "18") (pinfunction "18_18") (pintype "passive"))
      (node (ref "TP9") (pin "TP") (pinfunction "TP_TP") (pintype "input"))
    )
    (net (code "55") (name "UI") (class "Default")
      (node (ref "SV1") (pin "20") (pinfunction "20_20") (pintype "passive"))
      (node (ref "TP7") (pin "TP") (pinfunction "TP_TP") (pintype "input"))
    )
    (net (code "56") (name "unconnected-(IC1-PB6(XTAL1{slash}TOSC1)-Pad7)") (class "Default")
      (node (ref "IC1") (pin "7") (pinfunction "PB6(XTAL1/TOSC1)_7") (pintype "bidirectional"))
    )
    (net (code "57") (name "unconnected-(IC1-PB7(XTAL2{slash}TOSC2)-Pad8)") (class "Default")
      (node (ref "IC1") (pin "8") (pinfunction "PB7(XTAL2/TOSC2)_8") (pintype "bidirectional"))
    )
    (net (code "58") (name "unconnected-(IC1-PD1(TXD)-Pad31)") (class "Default")
      (node (ref "IC1") (pin "31") (pinfunction "PD1(TXD)_31") (pintype "bidirectional"))
    )
    (net (code "59") (name "unconnected-(LED16-DO-Pad2-DOUT)") (class "Default")
      (node (ref "LED16") (pin "2-DOUT") (pinfunction "DO_2-DOUT") (pintype "output"))
    )
    (net (code "60") (name "~{BALL_RST}") (class "Default")
      (node (ref "IC1") (pin "30") (pinfunction "PD0(RXD)_30") (pintype "bidirectional"))
      (node (ref "R4") (pin "1") (pinfunction "1_1") (pintype "passive"))
    )
    (net (code "61") (name "~{RESET}") (class "Default")
      (node (ref "IC1") (pin "29") (pinfunction "PC6(/RESET)_29") (pintype "bidirectional"))
      (node (ref "R2") (pin "2") (pinfunction "2_2") (pintype "passive"))
      (node (ref "SV1") (pin "15") (pinfunction "15_15") (pintype "passive"))
    )
  )
)
